# Battery_Voltage_12v_Max.net
KiCad netlist of a schematic drawn in Altium Designer
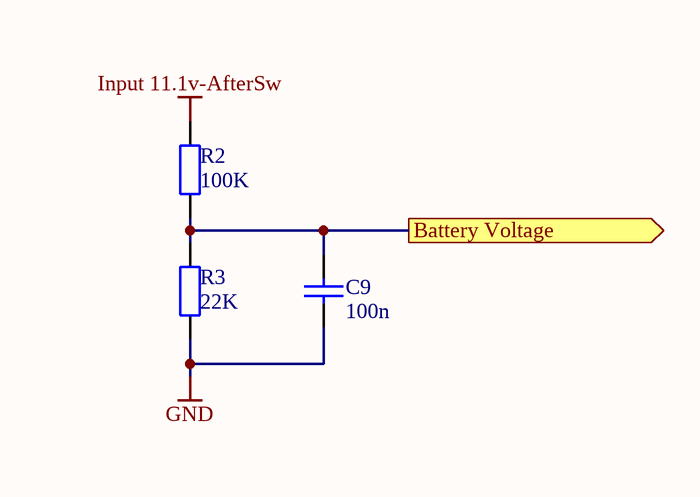
[diagram p0: Battery Voltage 12v Max.SchDoc]

(export (version "E")
  (design (tool "Eeschema 10.0.6"))
  (components
    (comp (ref "C9")
      (value "100n")
      (footprint "C0805")
      (fields (field (name "TOLERANCE") "0.1") (field (name "AUTHOR") "Willy Pietersz"))
      (libsource (lib "OurDb") (part "cap_NonPolar"))
    )
    (comp (ref "R2")
      (value "100K")
      (footprint "R0805")
      (description "Resistor")
      (fields
        (field (name "POWER") "0.25W")
        (field (name "TOLERANCE") "0.05")
        (field (name "PUBLISHER") "Altium Limited")
        (field (name "AUTHOR") "Willy Pietersz")
      )
      (libsource (lib "OurDb") (part "RESISTOR"))
    )
    (comp (ref "R3")
      (value "22K")
      (footprint "R0805")
      (description "Resistor")
      (fields
        (field (name "POWER") "0.25W")
        (field (name "TOLERANCE") "0.05")
        (field (name "PUBLISHER") "Altium Limited")
        (field (name "AUTHOR") "Willy Pietersz")
      )
      (libsource (lib "OurDb") (part "RESISTOR"))
    )
  )
  (nets
    (net (code "1") (name "/Battery Voltage") (class "Default")
      (node (ref "C9") (pin "2") (pinfunction "2_2") (pintype "passive"))
      (node (ref "R2") (pin "2") (pinfunction "2_2") (pintype "passive"))
      (node (ref "R3") (pin "1") (pinfunction "1_1") (pintype "passive"))
    )
    (net (code "2") (name "GND") (class "Default")
      (node (ref "C9") (pin "1") (pinfunction "1_1") (pintype "passive"))
      (node (ref "R3") (pin "2") (pinfunction "2_2") (pintype "passive"))
    )
    (net (code "3") (name "Input 11.1v-AfterSw") (class "Default")
      (node (ref "R2") (pin "1") (pinfunction "1_1") (pintype "passive"))
    )
  )
)
